# Driver.net
KiCad netlist of a schematic drawn in Altium Designer
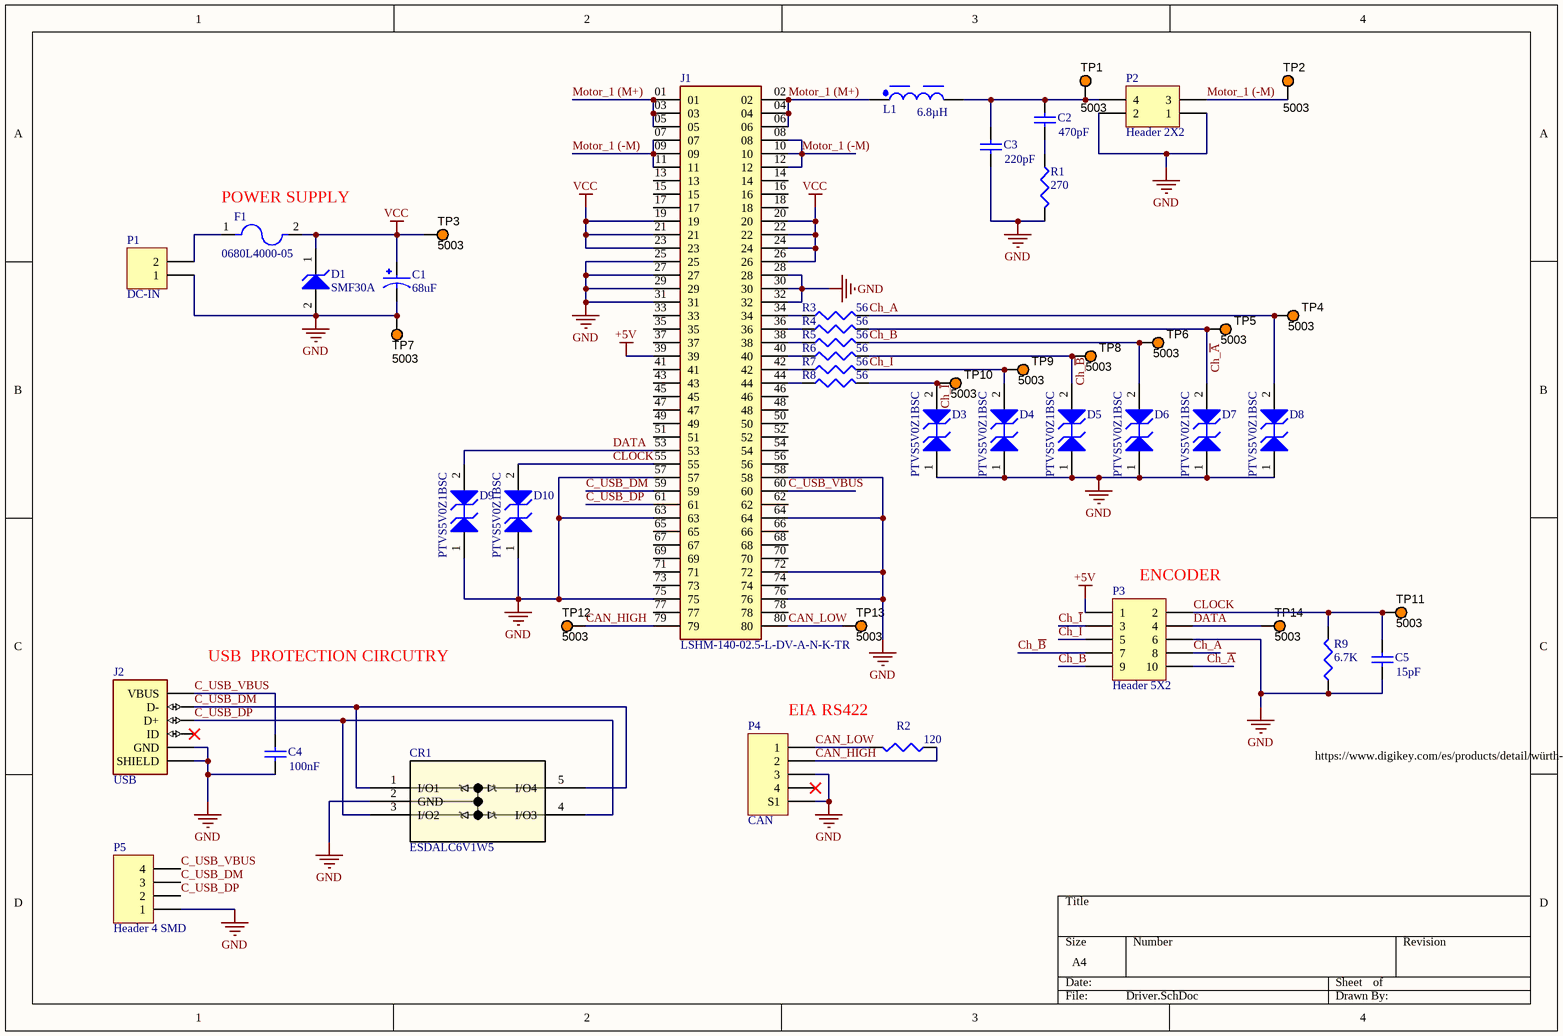
[diagram p0: Driver.SchDoc]

(export (version "E")
  (design (tool "Eeschema 10.0.6"))
  (components
    (comp (ref "C1")
      (value "68uF")
      (footprint "CAP_50SVT68M")
      (fields (field (name "MP") "50SVT68M"))
      (libsource (lib "DriverLib") (part "50SVT68M"))
    )
    (comp (ref "C2")
      (value "470pF")
      (footprint "1608[0603]")
      (description "Capacitor (Semiconductor SIM Model)")
      (fields (field (name "Comment") "Cap Semi") (field (name "PUBLISHER") "Altium Limited"))
      (libsource (lib "Miscellaneous Devices") (part "Cap Semi"))
    )
    (comp (ref "C3")
      (value "220pF")
      (footprint "1608[0603]")
      (description "Capacitor (Semiconductor SIM Model)")
      (fields (field (name "Comment") "Cap Semi") (field (name "PUBLISHER") "Altium Limited"))
      (libsource (lib "Miscellaneous Devices") (part "Cap Semi"))
    )
    (comp (ref "C4")
      (value "100nF")
      (footprint "1608[0603]")
      (description "Capacitor (Semiconductor SIM Model)")
      (fields (field (name "Comment") "Cap Semi") (field (name "PUBLISHER") "Altium Limited"))
      (libsource (lib "Miscellaneous Devices") (part "Cap Semi"))
    )
    (comp (ref "C5")
      (value "15pF")
      (footprint "1608[0603]")
      (description "Capacitor (Semiconductor SIM Model)")
      (fields (field (name "Comment") "Cap Semi") (field (name "PUBLISHER") "Altium Limited"))
      (libsource (lib "Miscellaneous Devices") (part "Cap Semi"))
    )
    (comp (ref "CR1")
      (value "ESDALC6V1W5")
      (footprint "ESDALC6V1W5-Footprint-1")
      (description "No Description Available")
      (fields (field (name "COPYRIGHT") "Copyright (C) 2022 Ultra Librarian. All rights reserved."))
      (libsource (lib "Universidad Nacional de Cordoba") (part "ESDALC6V1W5"))
    )
    (comp (ref "D1")
      (value "SMF30A")
      (footprint "ONSC-SOD-123FL-2-498_V")
      (description "200 W Transient Voltage Suppressor, 2-Pin SOD-123FL, Pb-Free, Tape and Reel")
      (fields (field (name "MANUFACTURER") "On Semiconductor") (field (name "PARTNUMBER") "SMF30AT1G"))
      (libsource (lib "ON Semi Transient Voltage Suppressors (TVS)") (part "SMF30AT1G"))
    )
    (comp (ref "D3")
      (value "PTVS5V0Z1BSC")
      (footprint "SOD993B")
      (fields (field (name "MANUFACTURER") "On Semiconductor") (field (name "PARTNUMBER") "1SMB16CAT3"))
      (libsource (lib "SpaceBee") (part "PTVS5V0Z1BSC"))
    )
    (comp (ref "D4")
      (value "PTVS5V0Z1BSC")
      (footprint "SOD993B")
      (fields (field (name "MANUFACTURER") "On Semiconductor") (field (name "PARTNUMBER") "1SMB16CAT3"))
      (libsource (lib "SpaceBee") (part "PTVS5V0Z1BSC"))
    )
    (comp (ref "D5")
      (value "PTVS5V0Z1BSC")
      (footprint "SOD993B")
      (fields (field (name "MANUFACTURER") "On Semiconductor") (field (name "PARTNUMBER") "1SMB16CAT3"))
      (libsource (lib "SpaceBee") (part "PTVS5V0Z1BSC"))
    )
    (comp (ref "D6")
      (value "PTVS5V0Z1BSC")
      (footprint "SOD993B")
      (fields (field (name "MANUFACTURER") "On Semiconductor") (field (name "PARTNUMBER") "1SMB16CAT3"))
      (libsource (lib "SpaceBee") (part "PTVS5V0Z1BSC"))
    )
    (comp (ref "D7")
      (value "PTVS5V0Z1BSC")
      (footprint "SOD993B")
      (fields (field (name "MANUFACTURER") "On Semiconductor") (field (name "PARTNUMBER") "1SMB16CAT3"))
      (libsource (lib "SpaceBee") (part "PTVS5V0Z1BSC"))
    )
    (comp (ref "D8")
      (value "PTVS5V0Z1BSC")
      (footprint "SOD993B")
      (fields (field (name "MANUFACTURER") "On Semiconductor") (field (name "PARTNUMBER") "1SMB16CAT3"))
      (libsource (lib "SpaceBee") (part "PTVS5V0Z1BSC"))
    )
    (comp (ref "D9")
      (value "PTVS5V0Z1BSC")
      (footprint "SOD993B")
      (fields (field (name "MANUFACTURER") "On Semiconductor") (field (name "PARTNUMBER") "1SMB16CAT3"))
      (libsource (lib "DriverLib") (part "PTVS5V0Z1BSC"))
    )
    (comp (ref "D10")
      (value "PTVS5V0Z1BSC")
      (footprint "SOD993B")
      (fields (field (name "MANUFACTURER") "On Semiconductor") (field (name "PARTNUMBER") "1SMB16CAT3"))
      (libsource (lib "DriverLib") (part "PTVS5V0Z1BSC"))
    )
    (comp (ref "F1")
      (value "0680L4000-05")
      (footprint "FUSC6125X279N")
      (description "Surface mount bricks ¦ Silver Plated ¦ 2410 case size ¦ Slow Blow ¦ 4A ¦ Tape and Reel (5000 pcs.)")
      (fields (field (name "MF") "Bel Fuse"))
      (libsource (lib "DriverLib") (part "0680L4000-05"))
    )
    (comp (ref "J1")
      (value "LSHM-140-02.5-L-DV-A-N-K-TR")
      (footprint "SAMTEC_LSHM-140-02.5-L-DV-A-N-K-TR")
      (description "LSHM - Samtec 0.50mm Razor Beam High-Speed Hermaphroditic Terminal / Socket Strip.")
      (libsource (lib "SpaceBee") (part "LSHM-140-02.5-L-DV-A-N-K-TR"))
    )
    (comp (ref "J2")
      (value "USB")
      (footprint "GCT_USB3076-XX-X_REVC")
      (fields (field (name "MP") "USB3076-XX-X_REVC"))
      (libsource (lib "DriverLib") (part "USB3076-XX-X_REVC"))
    )
    (comp (ref "L1")
      (value "6.8µH")
      (footprint "WE-XHMA_6060")
      (description "WE-XHMA SMD Power Inductor, size 1090, 6.8µH, 10.5A, 7.16mΩ")
      (fields
        (field (name "MANUFACTURER PART NUMBER") "78439369068")
        (field (name "MANUFACTURER") "Wurth Elektronik")
      )
      (libsource (lib "DriverLib") (part "78439369068"))
    )
    (comp (ref "P1")
      (value "DC-IN")
      (footprint "Header 2-Footprint-1")
      (description "Header, 2-Pin")
      (fields (field (name "PUBLISHER") "Altium Limited"))
      (libsource (lib "Universidad Nacional de Cordoba") (part "Header 2"))
    )
    (comp (ref "P2")
      (value "Header 2X2")
      (footprint "MOLEX_1724480004")
      (description "Header, 2-Pin, Dual row")
      (fields (field (name "PUBLISHER") "Altium Limited"))
      (libsource (lib "Universidad Nacional de Cordoba") (part "Header 2X2"))
    )
    (comp (ref "P3")
      (value "Header 5X2")
      (footprint "CONN_HIF3FC-14PA-2.54DS(71)_HIR")
      (description "Header, 5-Pin, Dual row")
      (fields (field (name "PUBLISHER") "Altium Limited"))
      (libsource (lib "DriverLib") (part "Header 5X2"))
    )
    (comp (ref "P4")
      (value "CAN")
      (footprint "MOLEX_5025850470")
      (description "Header, 5-Pin")
      (fields (field (name "PUBLISHER") "Altium Limited"))
      (libsource (lib "DriverLib") (part "Header 5"))
    )
    (comp (ref "P5")
      (value "Header 4 SMD")
      (footprint "Header 4 SMD")
      (description "Header, 4-Pin")
      (fields (field (name "PUBLISHER") "Altium Limited"))
      (libsource (lib "SpaceBee") (part "Header 4 SMD"))
    )
    (comp (ref "R1")
      (value "270")
      (footprint "J1-0603")
      (description "Resistor")
      (fields (field (name "Comment") "Res3") (field (name "PUBLISHER") "Altium Limited"))
      (libsource (lib "Miscellaneous Devices") (part "Res3"))
    )
    (comp (ref "R2")
      (value "120")
      (footprint "J1-0603")
      (description "Resistor")
      (fields (field (name "Comment") "Res3") (field (name "PUBLISHER") "Altium Limited"))
      (libsource (lib "Miscellaneous Devices") (part "Res3"))
    )
    (comp (ref "R3")
      (value "56")
      (footprint "J1-0603")
      (description "Resistor")
      (fields (field (name "Comment") "Res3") (field (name "PUBLISHER") "Altium Limited"))
      (libsource (lib "Miscellaneous Devices") (part "Res3"))
    )
    (comp (ref "R4")
      (value "56")
      (footprint "J1-0603")
      (description "Resistor")
      (fields (field (name "Comment") "Res3") (field (name "PUBLISHER") "Altium Limited"))
      (libsource (lib "Miscellaneous Devices") (part "Res3"))
    )
    (comp (ref "R5")
      (value "56")
      (footprint "J1-0603")
      (description "Resistor")
      (fields (field (name "Comment") "Res3") (field (name "PUBLISHER") "Altium Limited"))
      (libsource (lib "Miscellaneous Devices") (part "Res3"))
    )
    (comp (ref "R6")
      (value "56")
      (footprint "J1-0603")
      (description "Resistor")
      (fields (field (name "Comment") "Res3") (field (name "PUBLISHER") "Altium Limited"))
      (libsource (lib "Miscellaneous Devices") (part "Res3"))
    )
    (comp (ref "R7")
      (value "56")
      (footprint "J1-0603")
      (description "Resistor")
      (fields (field (name "Comment") "Res3") (field (name "PUBLISHER") "Altium Limited"))
      (libsource (lib "Miscellaneous Devices") (part "Res3"))
    )
    (comp (ref "R8")
      (value "56")
      (footprint "J1-0603")
      (description "Resistor")
      (fields (field (name "Comment") "Res3") (field (name "PUBLISHER") "Altium Limited"))
      (libsource (lib "Miscellaneous Devices") (part "Res3"))
    )
    (comp (ref "R9")
      (value "6.7K")
      (footprint "J1-0603")
      (description "Resistor")
      (fields (field (name "Comment") "Res3") (field (name "PUBLISHER") "Altium Limited"))
      (libsource (lib "Miscellaneous Devices") (part "Res3"))
    )
    (comp (ref "TP1")
      (value "5003")
      (footprint "KSTN-5003")
      (description "Test Point, Orange, Height 4.6 mm, Tail Length 3 mm, 1-Pin THD, RoHS")
      (fields (field (name "MANUFACTURER") "Keystone"))
      (libsource (lib "Universidad Nacional de Cordoba") (part "TESTPOINT_ORANGE"))
    )
    (comp (ref "TP2")
      (value "5003")
      (footprint "KSTN-5003")
      (description "Test Point, Orange, Height 4.6 mm, Tail Length 3 mm, 1-Pin THD, RoHS")
      (fields (field (name "MANUFACTURER") "Keystone"))
      (libsource (lib "Universidad Nacional de Cordoba") (part "TESTPOINT_ORANGE"))
    )
    (comp (ref "TP3")
      (value "5003")
      (footprint "KSTN-5003")
      (description "Test Point, Orange, Height 4.6 mm, Tail Length 3 mm, 1-Pin THD, RoHS")
      (fields (field (name "MANUFACTURER") "Keystone"))
      (libsource (lib "Universidad Nacional de Cordoba") (part "TESTPOINT_ORANGE"))
    )
    (comp (ref "TP4")
      (value "5003")
      (footprint "KSTN-5003")
      (description "Test Point, Orange, Height 4.6 mm, Tail Length 3 mm, 1-Pin THD, RoHS")
      (fields (field (name "MANUFACTURER") "Keystone"))
      (libsource (lib "Universidad Nacional de Cordoba") (part "TESTPOINT_ORANGE"))
    )
    (comp (ref "TP5")
      (value "5003")
      (footprint "KSTN-5003")
      (description "Test Point, Orange, Height 4.6 mm, Tail Length 3 mm, 1-Pin THD, RoHS")
      (fields (field (name "MANUFACTURER") "Keystone"))
      (libsource (lib "Universidad Nacional de Cordoba") (part "TESTPOINT_ORANGE"))
    )
    (comp (ref "TP6")
      (value "5003")
      (footprint "KSTN-5003")
      (description "Test Point, Orange, Height 4.6 mm, Tail Length 3 mm, 1-Pin THD, RoHS")
      (fields (field (name "MANUFACTURER") "Keystone"))
      (libsource (lib "Universidad Nacional de Cordoba") (part "TESTPOINT_ORANGE"))
    )
    (comp (ref "TP7")
      (value "5003")
      (footprint "KSTN-5003")
      (description "Test Point, Orange, Height 4.6 mm, Tail Length 3 mm, 1-Pin THD, RoHS")
      (fields (field (name "MANUFACTURER") "Keystone"))
      (libsource (lib "Universidad Nacional de Cordoba") (part "TESTPOINT_ORANGE"))
    )
    (comp (ref "TP8")
      (value "5003")
      (footprint "KSTN-5003")
      (description "Test Point, Orange, Height 4.6 mm, Tail Length 3 mm, 1-Pin THD, RoHS")
      (fields (field (name "MANUFACTURER") "Keystone"))
      (libsource (lib "Universidad Nacional de Cordoba") (part "TESTPOINT_ORANGE"))
    )
    (comp (ref "TP9")
      (value "5003")
      (footprint "KSTN-5003")
      (description "Test Point, Orange, Height 4.6 mm, Tail Length 3 mm, 1-Pin THD, RoHS")
      (fields (field (name "MANUFACTURER") "Keystone"))
      (libsource (lib "Universidad Nacional de Cordoba") (part "TESTPOINT_ORANGE"))
    )
    (comp (ref "TP10")
      (value "5003")
      (footprint "KSTN-5003")
      (description "Test Point, Orange, Height 4.6 mm, Tail Length 3 mm, 1-Pin THD, RoHS")
      (fields (field (name "MANUFACTURER") "Keystone"))
      (libsource (lib "Universidad Nacional de Cordoba") (part "TESTPOINT_ORANGE"))
    )
    (comp (ref "TP11")
      (value "5003")
      (footprint "KSTN-5003")
      (description "Test Point, Orange, Height 4.6 mm, Tail Length 3 mm, 1-Pin THD, RoHS")
      (fields (field (name "MANUFACTURER") "Keystone"))
      (libsource (lib "Universidad Nacional de Cordoba") (part "TESTPOINT_ORANGE"))
    )
    (comp (ref "TP12")
      (value "5003")
      (footprint "KSTN-5003")
      (description "Test Point, Orange, Height 4.6 mm, Tail Length 3 mm, 1-Pin THD, RoHS")
      (fields (field (name "MANUFACTURER") "Keystone"))
      (libsource (lib "Universidad Nacional de Cordoba") (part "TESTPOINT_ORANGE"))
    )
    (comp (ref "TP13")
      (value "5003")
      (footprint "KSTN-5003")
      (description "Test Point, Orange, Height 4.6 mm, Tail Length 3 mm, 1-Pin THD, RoHS")
      (fields (field (name "MANUFACTURER") "Keystone"))
      (libsource (lib "Universidad Nacional de Cordoba") (part "TESTPOINT_ORANGE"))
    )
    (comp (ref "TP14")
      (value "5003")
      (footprint "KSTN-5003")
      (description "Test Point, Orange, Height 4.6 mm, Tail Length 3 mm, 1-Pin THD, RoHS")
      (fields (field (name "MANUFACTURER") "Keystone"))
      (libsource (lib "Universidad Nacional de Cordoba") (part "TESTPOINT_ORANGE"))
    )
  )
  (nets
    (net (code "1") (name "+5V") (class "Default")
      (node (ref "J1") (pin "39") (pinfunction "39_39") (pintype "passive"))
      (node (ref "P3") (pin "1") (pinfunction "1_1") (pintype "passive"))
    )
    (net (code "2") (name "/CAN_HIGH") (class "Default")
      (node (ref "J1") (pin "79") (pinfunction "79_79") (pintype "passive"))
      (node (ref "P4") (pin "2") (pinfunction "2_2") (pintype "passive"))
      (node (ref "R2") (pin "1") (pinfunction "1_1") (pintype "passive"))
      (node (ref "TP12") (pin "1") (pinfunction "1_1") (pintype "passive"))
    )
    (net (code "3") (name "/CAN_LOW") (class "Default")
      (node (ref "J1") (pin "80") (pinfunction "80_80") (pintype "passive"))
      (node (ref "P4") (pin "1") (pinfunction "1_1") (pintype "passive"))
      (node (ref "R2") (pin "2") (pinfunction "2_2") (pintype "passive"))
      (node (ref "TP13") (pin "1") (pinfunction "1_1") (pintype "passive"))
    )
    (net (code "4") (name "/CLOCK") (class "Default")
      (node (ref "C5") (pin "1") (pinfunction "1_1") (pintype "passive"))
      (node (ref "D10") (pin "2") (pinfunction "A2_2") (pintype "passive"))
      (node (ref "J1") (pin "55") (pinfunction "55_55") (pintype "passive"))
      (node (ref "P3") (pin "2") (pinfunction "2_2") (pintype "passive"))
      (node (ref "R9") (pin "2") (pinfunction "2_2") (pintype "passive"))
      (node (ref "TP11") (pin "1") (pinfunction "1_1") (pintype "passive"))
    )
    (net (code "5") (name "/C_USB_DM") (class "Default")
      (node (ref "CR1") (pin "1") (pinfunction "I/O1_1") (pintype "passive"))
      (node (ref "CR1") (pin "5") (pinfunction "I/O4_5") (pintype "passive"))
      (node (ref "J1") (pin "59") (pinfunction "59_59") (pintype "passive"))
      (node (ref "J2") (pin "2") (pinfunction "D-_2") (pintype "bidirectional"))
      (node (ref "P5") (pin "3") (pinfunction "3_3") (pintype "passive"))
    )
    (net (code "6") (name "/C_USB_DP") (class "Default")
      (node (ref "CR1") (pin "3") (pinfunction "I/O2_3") (pintype "passive"))
      (node (ref "CR1") (pin "4") (pinfunction "I/O3_4") (pintype "passive"))
      (node (ref "J1") (pin "61") (pinfunction "61_61") (pintype "passive"))
      (node (ref "J2") (pin "3") (pinfunction "D+_3") (pintype "bidirectional"))
      (node (ref "P5") (pin "2") (pinfunction "2_2") (pintype "passive"))
    )
    (net (code "7") (name "/C_USB_VBUS") (class "Default")
      (node (ref "C4") (pin "1") (pinfunction "1_1") (pintype "passive"))
      (node (ref "J1") (pin "60") (pinfunction "60_60") (pintype "passive"))
      (node (ref "J2") (pin "1") (pinfunction "VBUS_1") (pintype "power_in"))
      (node (ref "P5") (pin "4") (pinfunction "4_4") (pintype "passive"))
    )
    (net (code "8") (name "/Ch_A") (class "Default")
      (node (ref "D8") (pin "2") (pinfunction "A2_2") (pintype "passive"))
      (node (ref "P3") (pin "8") (pinfunction "8_8") (pintype "passive"))
      (node (ref "R3") (pin "2") (pinfunction "2_2") (pintype "passive"))
      (node (ref "TP4") (pin "1") (pinfunction "1_1") (pintype "passive"))
    )
    (net (code "9") (name "/Ch_B") (class "Default")
      (node (ref "D6") (pin "2") (pinfunction "A2_2") (pintype "passive"))
      (node (ref "P3") (pin "9") (pinfunction "9_9") (pintype "passive"))
      (node (ref "R5") (pin "2") (pinfunction "2_2") (pintype "passive"))
      (node (ref "TP6") (pin "1") (pinfunction "1_1") (pintype "passive"))
    )
    (net (code "10") (name "/Ch_I") (class "Default")
      (node (ref "D4") (pin "2") (pinfunction "A2_2") (pintype "passive"))
      (node (ref "P3") (pin "5") (pinfunction "5_5") (pintype "passive"))
      (node (ref "R7") (pin "2") (pinfunction "2_2") (pintype "passive"))
      (node (ref "TP9") (pin "1") (pinfunction "1_1") (pintype "passive"))
    )
    (net (code "11") (name "/Ch_~{A}") (class "Default")
      (node (ref "D7") (pin "2") (pinfunction "A2_2") (pintype "passive"))
      (node (ref "P3") (pin "10") (pinfunction "10_10") (pintype "passive"))
      (node (ref "R4") (pin "2") (pinfunction "2_2") (pintype "passive"))
      (node (ref "TP5") (pin "1") (pinfunction "1_1") (pintype "passive"))
    )
    (net (code "12") (name "/Ch_~{B}") (class "Default")
      (node (ref "D5") (pin "2") (pinfunction "A2_2") (pintype "passive"))
      (node (ref "P3") (pin "7") (pinfunction "7_7") (pintype "passive"))
      (node (ref "R6") (pin "2") (pinfunction "2_2") (pintype "passive"))
      (node (ref "TP8") (pin "1") (pinfunction "1_1") (pintype "passive"))
    )
    (net (code "13") (name "/Ch_~{I}") (class "Default")
      (node (ref "D3") (pin "2") (pinfunction "A2_2") (pintype "passive"))
      (node (ref "P3") (pin "3") (pinfunction "3_3") (pintype "passive"))
      (node (ref "R8") (pin "2") (pinfunction "2_2") (pintype "passive"))
      (node (ref "TP10") (pin "1") (pinfunction "1_1") (pintype "passive"))
    )
    (net (code "14") (name "/DATA") (class "Default")
      (node (ref "D9") (pin "2") (pinfunction "A2_2") (pintype "passive"))
      (node (ref "J1") (pin "53") (pinfunction "53_53") (pintype "passive"))
      (node (ref "P3") (pin "4") (pinfunction "4_4") (pintype "passive"))
      (node (ref "TP14") (pin "1") (pinfunction "1_1") (pintype "passive"))
    )
    (net (code "15") (name "/Motor_1 (-M)") (class "Default")
      (node (ref "J1") (pin "07") (pinfunction "07_07") (pintype "passive"))
      (node (ref "J1") (pin "08") (pinfunction "08_08") (pintype "passive"))
      (node (ref "J1") (pin "09") (pinfunction "09_09") (pintype "passive"))
      (node (ref "J1") (pin "10") (pinfunction "10_10") (pintype "passive"))
      (node (ref "J1") (pin "11") (pinfunction "11_11") (pintype "passive"))
      (node (ref "J1") (pin "12") (pinfunction "12_12") (pintype "passive"))
      (node (ref "P2") (pin "3") (pinfunction "3_3") (pintype "passive"))
      (node (ref "TP2") (pin "1") (pinfunction "1_1") (pintype "passive"))
    )
    (net (code "16") (name "/Motor_1 (M+)") (class "Default")
      (node (ref "J1") (pin "01") (pinfunction "01_01") (pintype "passive"))
      (node (ref "J1") (pin "02") (pinfunction "02_02") (pintype "passive"))
      (node (ref "J1") (pin "03") (pinfunction "03_03") (pintype "passive"))
      (node (ref "J1") (pin "04") (pinfunction "04_04") (pintype "passive"))
      (node (ref "J1") (pin "05") (pinfunction "05_05") (pintype "passive"))
      (node (ref "J1") (pin "06") (pinfunction "06_06") (pintype "passive"))
      (node (ref "L1") (pin "1") (pinfunction "1_1") (pintype "passive"))
    )
    (net (code "17") (name "GND") (class "Default")
      (node (ref "C1") (pin "2") (pinfunction "2_2") (pintype "passive"))
      (node (ref "C3") (pin "2") (pinfunction "2_2") (pintype "passive"))
      (node (ref "C4") (pin "2") (pinfunction "2_2") (pintype "passive"))
      (node (ref "C5") (pin "2") (pinfunction "2_2") (pintype "passive"))
      (node (ref "CR1") (pin "2") (pinfunction "GND_2") (pintype "passive"))
      (node (ref "D1") (pin "2") (pinfunction "A_2") (pintype "passive"))
      (node (ref "D10") (pin "1") (pinfunction "A1_1") (pintype "passive"))
      (node (ref "D3") (pin "1") (pinfunction "A1_1") (pintype "passive"))
      (node (ref "D4") (pin "1") (pinfunction "A1_1") (pintype "passive"))
      (node (ref "D5") (pin "1") (pinfunction "A1_1") (pintype "passive"))
      (node (ref "D6") (pin "1") (pinfunction "A1_1") (pintype "passive"))
      (node (ref "D7") (pin "1") (pinfunction "A1_1") (pintype "passive"))
      (node (ref "D8") (pin "1") (pinfunction "A1_1") (pintype "passive"))
      (node (ref "D9") (pin "1") (pinfunction "A1_1") (pintype "passive"))
      (node (ref "J1") (pin "25") (pinfunction "25_25") (pintype "passive"))
      (node (ref "J1") (pin "27") (pinfunction "27_27") (pintype "passive"))
      (node (ref "J1") (pin "28") (pinfunction "28_28") (pintype "passive"))
      (node (ref "J1") (pin "29") (pinfunction "29_29") (pintype "passive"))
      (node (ref "J1") (pin "30") (pinfunction "30_30") (pintype "passive"))
      (node (ref "J1") (pin "31") (pinfunction "31_31") (pintype "passive"))
      (node (ref "J1") (pin "32") (pinfunction "32_32") (pintype "passive"))
      (node (ref "J1") (pin "57") (pinfunction "57_57") (pintype "passive"))
      (node (ref "J1") (pin "58") (pinfunction "58_58") (pintype "passive"))
      (node (ref "J1") (pin "63") (pinfunction "63_63") (pintype "passive"))
      (node (ref "J1") (pin "64") (pinfunction "64_64") (pintype "passive"))
      (node (ref "J1") (pin "72") (pinfunction "72_72") (pintype "passive"))
      (node (ref "J1") (pin "75") (pinfunction "75_75") (pintype "passive"))
      (node (ref "J1") (pin "76") (pinfunction "76_76") (pintype "passive"))
      (node (ref "J2") (pin "5") (pinfunction "GND_5") (pintype "power_in"))
      (node (ref "J2") (pin "6") (pinfunction "SHIELD_6") (pintype "power_in"))
      (node (ref "P1") (pin "1") (pinfunction "1_1") (pintype "passive"))
      (node (ref "P2") (pin "1") (pinfunction "1_1") (pintype "passive"))
      (node (ref "P2") (pin "2") (pinfunction "2_2") (pintype "passive"))
      (node (ref "P3") (pin "6") (pinfunction "6_6") (pintype "passive"))
      (node (ref "P4") (pin "3") (pinfunction "3_3") (pintype "passive"))
      (node (ref "P4") (pin "S1") (pinfunction "S1_S1") (pintype "passive"))
      (node (ref "P5") (pin "1") (pinfunction "1_1") (pintype "passive"))
      (node (ref "R1") (pin "2") (pinfunction "2_2") (pintype "passive"))
      (node (ref "R9") (pin "1") (pinfunction "1_1") (pintype "passive"))
      (node (ref "TP7") (pin "1") (pinfunction "1_1") (pintype "passive"))
    )
    (net (code "18") (name "Net-(C2-Pad1)") (class "Default")
      (node (ref "C2") (pin "1") (pinfunction "1_1") (pintype "passive"))
      (node (ref "C3") (pin "1") (pinfunction "1_1") (pintype "passive"))
      (node (ref "L1") (pin "2") (pinfunction "2_2") (pintype "passive"))
      (node (ref "P2") (pin "4") (pinfunction "4_4") (pintype "passive"))
      (node (ref "TP1") (pin "1") (pinfunction "1_1") (pintype "passive"))
    )
    (net (code "19") (name "Net-(C2-Pad2)") (class "Default")
      (node (ref "C2") (pin "2") (pinfunction "2_2") (pintype "passive"))
      (node (ref "R1") (pin "1") (pinfunction "1_1") (pintype "passive"))
    )
    (net (code "20") (name "Net-(F1-Pad1)") (class "Default")
      (node (ref "F1") (pin "1") (pinfunction "1_1") (pintype "passive"))
      (node (ref "P1") (pin "2") (pinfunction "2_2") (pintype "passive"))
    )
    (net (code "21") (name "Net-(J1-Pad34)") (class "Default")
      (node (ref "J1") (pin "34") (pinfunction "34_34") (pintype "passive"))
      (node (ref "R3") (pin "1") (pinfunction "1_1") (pintype "passive"))
    )
    (net (code "22") (name "Net-(J1-Pad36)") (class "Default")
      (node (ref "J1") (pin "36") (pinfunction "36_36") (pintype "passive"))
      (node (ref "R4") (pin "1") (pinfunction "1_1") (pintype "passive"))
    )
    (net (code "23") (name "Net-(J1-Pad38)") (class "Default")
      (node (ref "J1") (pin "38") (pinfunction "38_38") (pintype "passive"))
      (node (ref "R5") (pin "1") (pinfunction "1_1") (pintype "passive"))
    )
    (net (code "24") (name "Net-(J1-Pad40)") (class "Default")
      (node (ref "J1") (pin "40") (pinfunction "40_40") (pintype "passive"))
      (node (ref "R6") (pin "1") (pinfunction "1_1") (pintype "passive"))
    )
    (net (code "25") (name "Net-(J1-Pad42)") (class "Default")
      (node (ref "J1") (pin "42") (pinfunction "42_42") (pintype "passive"))
      (node (ref "R7") (pin "1") (pinfunction "1_1") (pintype "passive"))
    )
    (net (code "26") (name "Net-(J1-Pad44)") (class "Default")
      (node (ref "J1") (pin "44") (pinfunction "44_44") (pintype "passive"))
      (node (ref "R8") (pin "1") (pinfunction "1_1") (pintype "passive"))
    )
    (net (code "27") (name "VCC") (class "Default")
      (node (ref "C1") (pin "1") (pinfunction "1_1") (pintype "passive"))
      (node (ref "D1") (pin "1") (pinfunction "K_1") (pintype "passive"))
      (node (ref "F1") (pin "2") (pinfunction "2_2") (pintype "passive"))
      (node (ref "J1") (pin "19") (pinfunction "19_19") (pintype "passive"))
      (node (ref "J1") (pin "20") (pinfunction "20_20") (pintype "passive"))
      (node (ref "J1") (pin "21") (pinfunction "21_21") (pintype "passive"))
      (node (ref "J1") (pin "22") (pinfunction "22_22") (pintype "passive"))
      (node (ref "J1") (pin "23") (pinfunction "23_23") (pintype "passive"))
      (node (ref "J1") (pin "24") (pinfunction "24_24") (pintype "passive"))
      (node (ref "J1") (pin "26") (pinfunction "26_26") (pintype "passive"))
      (node (ref "TP3") (pin "1") (pinfunction "1_1") (pintype "passive"))
    )
    (net (code "28") (name "unconnected-(J1-Pad13)") (class "Default")
      (node (ref "J1") (pin "13") (pinfunction "13_13") (pintype "passive"))
    )
    (net (code "29") (name "unconnected-(J1-Pad14)") (class "Default")
      (node (ref "J1") (pin "14") (pinfunction "14_14") (pintype "passive"))
    )
    (net (code "30") (name "unconnected-(J1-Pad15)") (class "Default")
      (node (ref "J1") (pin "15") (pinfunction "15_15") (pintype "passive"))
    )
    (net (code "31") (name "unconnected-(J1-Pad16)") (class "Default")
      (node (ref "J1") (pin "16") (pinfunction "16_16") (pintype "passive"))
    )
    (net (code "32") (name "unconnected-(J1-Pad17)") (class "Default")
      (node (ref "J1") (pin "17") (pinfunction "17_17") (pintype "passive"))
    )
    (net (code "33") (name "unconnected-(J1-Pad18)") (class "Default")
      (node (ref "J1") (pin "18") (pinfunction "18_18") (pintype "passive"))
    )
    (net (code "34") (name "unconnected-(J1-Pad33)") (class "Default")
      (node (ref "J1") (pin "33") (pinfunction "33_33") (pintype "passive"))
    )
    (net (code "35") (name "unconnected-(J1-Pad35)") (class "Default")
      (node (ref "J1") (pin "35") (pinfunction "35_35") (pintype "passive"))
    )
    (net (code "36") (name "unconnected-(J1-Pad37)") (class "Default")
      (node (ref "J1") (pin "37") (pinfunction "37_37") (pintype "passive"))
    )
    (net (code "37") (name "unconnected-(J1-Pad41)") (class "Default")
      (node (ref "J1") (pin "41") (pinfunction "41_41") (pintype "passive"))
    )
    (net (code "38") (name "unconnected-(J1-Pad43)") (class "Default")
      (node (ref "J1") (pin "43") (pinfunction "43_43") (pintype "passive"))
    )
    (net (code "39") (name "unconnected-(J1-Pad45)") (class "Default")
      (node (ref "J1") (pin "45") (pinfunction "45_45") (pintype "passive"))
    )
    (net (code "40") (name "unconnected-(J1-Pad46)") (class "Default")
      (node (ref "J1") (pin "46") (pinfunction "46_46") (pintype "passive"))
    )
    (net (code "41") (name "unconnected-(J1-Pad47)") (class "Default")
      (node (ref "J1") (pin "47") (pinfunction "47_47") (pintype "passive"))
    )
    (net (code "42") (name "unconnected-(J1-Pad48)") (class "Default")
      (node (ref "J1") (pin "48") (pinfunction "48_48") (pintype "passive"))
    )
    (net (code "43") (name "unconnected-(J1-Pad49)") (class "Default")
      (node (ref "J1") (pin "49") (pinfunction "49_49") (pintype "passive"))
    )
    (net (code "44") (name "unconnected-(J1-Pad50)") (class "Default")
      (node (ref "J1") (pin "50") (pinfunction "50_50") (pintype "passive"))
    )
    (net (code "45") (name "unconnected-(J1-Pad51)") (class "Default")
      (node (ref "J1") (pin "51") (pinfunction "51_51") (pintype "passive"))
    )
    (net (code "46") (name "unconnected-(J1-Pad52)") (class "Default")
      (node (ref "J1") (pin "52") (pinfunction "52_52") (pintype "passive"))
    )
    (net (code "47") (name "unconnected-(J1-Pad54)") (class "Default")
      (node (ref "J1") (pin "54") (pinfunction "54_54") (pintype "passive"))
    )
    (net (code "48") (name "unconnected-(J1-Pad56)") (class "Default")
      (node (ref "J1") (pin "56") (pinfunction "56_56") (pintype "passive"))
    )
    (net (code "49") (name "unconnected-(J1-Pad62)") (class "Default")
      (node (ref "J1") (pin "62") (pinfunction "62_62") (pintype "passive"))
    )
    (net (code "50") (name "unconnected-(J1-Pad65)") (class "Default")
      (node (ref "J1") (pin "65") (pinfunction "65_65") (pintype "passive"))
    )
    (net (code "51") (name "unconnected-(J1-Pad66)") (class "Default")
      (node (ref "J1") (pin "66") (pinfunction "66_66") (pintype "passive"))
    )
    (net (code "52") (name "unconnected-(J1-Pad67)") (class "Default")
      (node (ref "J1") (pin "67") (pinfunction "67_67") (pintype "passive"))
    )
    (net (code "53") (name "unconnected-(J1-Pad68)") (class "Default")
      (node (ref "J1") (pin "68") (pinfunction "68_68") (pintype "passive"))
    )
    (net (code "54") (name "unconnected-(J1-Pad69)") (class "Default")
      (node (ref "J1") (pin "69") (pinfunction "69_69") (pintype "passive"))
    )
    (net (code "55") (name "unconnected-(J1-Pad70)") (class "Default")
      (node (ref "J1") (pin "70") (pinfunction "70_70") (pintype "passive"))
    )
    (net (code "56") (name "unconnected-(J1-Pad71)") (class "Default")
      (node (ref "J1") (pin "71") (pinfunction "71_71") (pintype "passive"))
    )
    (net (code "57") (name "unconnected-(J1-Pad73)") (class "Default")
      (node (ref "J1") (pin "73") (pinfunction "73_73") (pintype "passive"))
    )
    (net (code "58") (name "unconnected-(J1-Pad74)") (class "Default")
      (node (ref "J1") (pin "74") (pinfunction "74_74") (pintype "passive"))
    )
    (net (code "59") (name "unconnected-(J1-Pad77)") (class "Default")
      (node (ref "J1") (pin "77") (pinfunction "77_77") (pintype "passive"))
    )
    (net (code "60") (name "unconnected-(J1-Pad78)") (class "Default")
      (node (ref "J1") (pin "78") (pinfunction "78_78") (pintype "passive"))
    )
    (net (code "61") (name "unconnected-(J2-ID-Pad4)") (class "Default")
      (node (ref "J2") (pin "4") (pinfunction "ID_4") (pintype "bidirectional+no_connect"))
    )
    (net (code "62") (name "unconnected-(P4-Pad4)") (class "Default")
      (node (ref "P4") (pin "4") (pinfunction "4_4") (pintype "passive+no_connect"))
    )
  )
)
